# Handle_2019_-_STM32.net
KiCad netlist of a schematic drawn in EAGLE
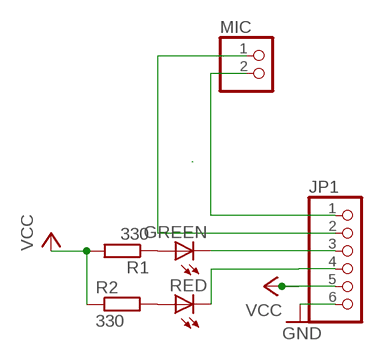
[diagram p0: schematic, sheet 1]

(export (version "E")
  (design (tool "Eeschema 10.0.6"))
  (components
    (comp (ref "GREEN")
      (value "LED5MM")
      (footprint "eagle-import:LED5MM")
      (libsource (lib "eagle-import") (part "LED5MM"))
    )
    (comp (ref "JP1")
      (value "PINHD-1X6")
      (footprint "eagle-import:1X06")
      (libsource (lib "eagle-import") (part "PINHD-1X6"))
    )
    (comp (ref "MIC")
      (value "PINHD-1X2")
      (footprint "eagle-import:1X02")
      (libsource (lib "eagle-import") (part "PINHD-1X2"))
    )
    (comp (ref "R1")
      (value "330")
      (footprint "eagle-import:M1206")
      (libsource (lib "eagle-import") (part "R-EU_M1206"))
    )
    (comp (ref "R2")
      (value "330")
      (footprint "eagle-import:M1206")
      (libsource (lib "eagle-import") (part "R-EU_M1206"))
    )
    (comp (ref "RED")
      (value "LED5MM")
      (footprint "eagle-import:LED5MM")
      (libsource (lib "eagle-import") (part "LED5MM"))
    )
  )
  (nets
    (net (code "1") (name "GND") (class "Default")
      (node (ref "JP1") (pin "6") (pinfunction "6_6") (pintype "passive"))
    )
    (net (code "2") (name "Net-(GREEN-C)") (class "Default")
      (node (ref "GREEN") (pin "K") (pinfunction "C_K") (pintype "passive"))
      (node (ref "JP1") (pin "3") (pinfunction "3_3") (pintype "passive"))
    )
    (net (code "3") (name "Net-(GREEN-PadA)") (class "Default")
      (node (ref "GREEN") (pin "A") (pinfunction "A_A") (pintype "passive"))
      (node (ref "R1") (pin "1") (pinfunction "1_1") (pintype "passive"))
    )
    (net (code "4") (name "Net-(JP1-Pad1)") (class "Default")
      (node (ref "JP1") (pin "1") (pinfunction "1_1") (pintype "passive"))
      (node (ref "MIC") (pin "2") (pinfunction "2_2") (pintype "passive"))
    )
    (net (code "5") (name "Net-(JP1-Pad2)") (class "Default")
      (node (ref "JP1") (pin "2") (pinfunction "2_2") (pintype "passive"))
      (node (ref "MIC") (pin "1") (pinfunction "1_1") (pintype "passive"))
    )
    (net (code "6") (name "Net-(R2-Pad2)") (class "Default")
      (node (ref "R2") (pin "2") (pinfunction "2_2") (pintype "passive"))
      (node (ref "RED") (pin "A") (pinfunction "A_A") (pintype "passive"))
    )
    (net (code "7") (name "Net-(RED-C)") (class "Default")
      (node (ref "JP1") (pin "4") (pinfunction "4_4") (pintype "passive"))
      (node (ref "RED") (pin "K") (pinfunction "C_K") (pintype "passive"))
    )
    (net (code "8") (name "VCC") (class "Default")
      (node (ref "JP1") (pin "5") (pinfunction "5_5") (pintype "passive"))
      (node (ref "R1") (pin "2") (pinfunction "2_2") (pintype "passive"))
      (node (ref "R2") (pin "1") (pinfunction "1_1") (pintype "passive"))
    )
  )
)
